# Beta22.net
KiCad netlist of a schematic drawn in EAGLE
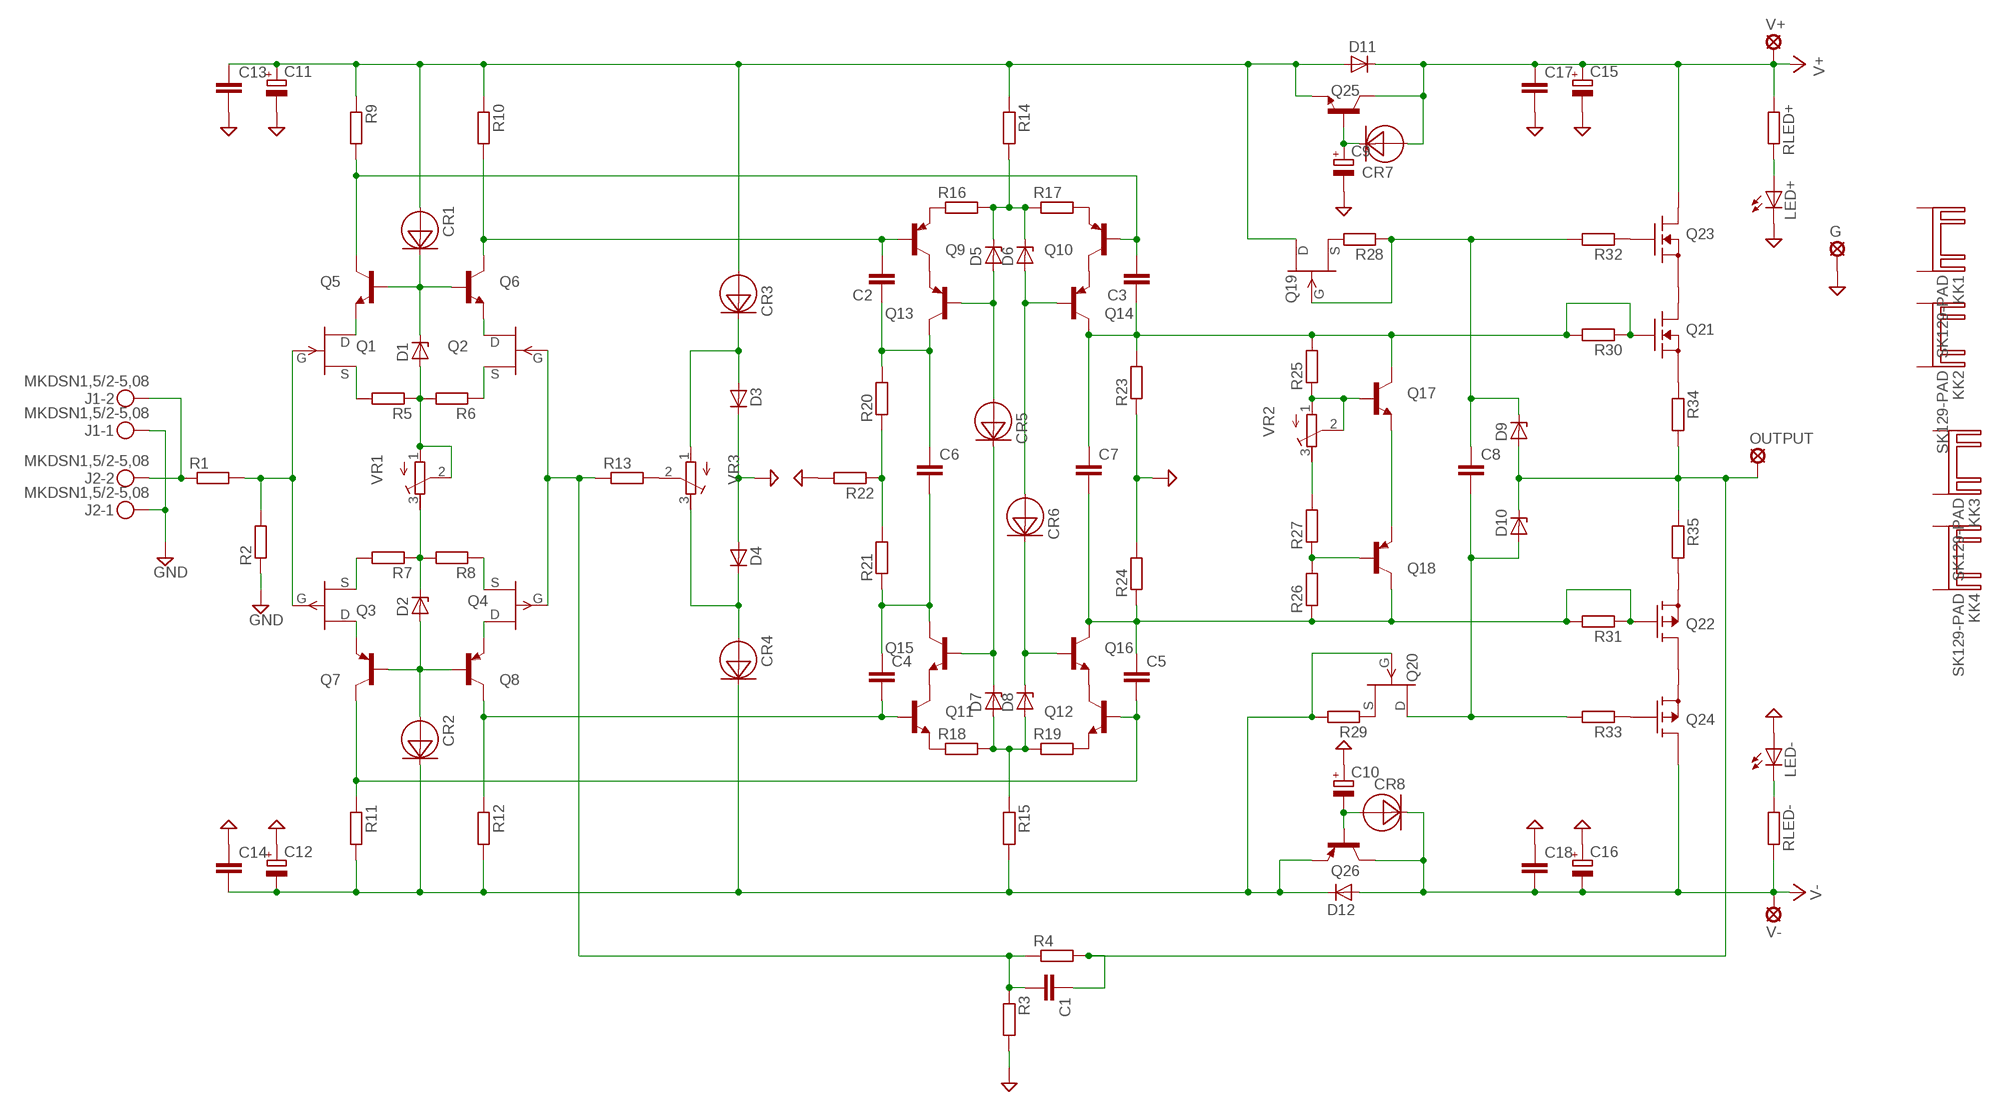
[diagram p0: schematic, sheet 1]

(export (version "E")
  (design (tool "Eeschema 10.0.6"))
  (components
    (comp (ref "C1")
      (value "C-EU025_050-025X075")
      (footprint "eagle-import:C025_050-025X075")
      (libsource (lib "eagle-import") (part "C-EU025_050-025X075"))
    )
    (comp (ref "C2")
      (value "C-EU025_050-025X075")
      (footprint "eagle-import:C025_050-025X075")
      (libsource (lib "eagle-import") (part "C-EU025_050-025X075"))
    )
    (comp (ref "C3")
      (value "C-EU025_050-025X075")
      (footprint "eagle-import:C025_050-025X075")
      (libsource (lib "eagle-import") (part "C-EU025_050-025X075"))
    )
    (comp (ref "C4")
      (value "C-EU025_050-025X075")
      (footprint "eagle-import:C025_050-025X075")
      (libsource (lib "eagle-import") (part "C-EU025_050-025X075"))
    )
    (comp (ref "C5")
      (value "C-EU025_050-025X075")
      (footprint "eagle-import:C025_050-025X075")
      (libsource (lib "eagle-import") (part "C-EU025_050-025X075"))
    )
    (comp (ref "C6")
      (value "C-EU050-055X075")
      (footprint "eagle-import:C050-055X075")
      (libsource (lib "eagle-import") (part "C-EU050-055X075"))
    )
    (comp (ref "C7")
      (value "C-EU050-055X075")
      (footprint "eagle-import:C050-055X075")
      (libsource (lib "eagle-import") (part "C-EU050-055X075"))
    )
    (comp (ref "C8")
      (value "C-EU050-055X075")
      (footprint "eagle-import:C050-055X075")
      (libsource (lib "eagle-import") (part "C-EU050-055X075"))
    )
    (comp (ref "C9")
      (value "CPOL-EUE5-13")
      (footprint "eagle-import:E5-13")
      (libsource (lib "eagle-import") (part "CPOL-EUE5-13"))
    )
    (comp (ref "C10")
      (value "CPOL-EUE5-13")
      (footprint "eagle-import:E5-13")
      (libsource (lib "eagle-import") (part "CPOL-EUE5-13"))
    )
    (comp (ref "C11")
      (value "CPOL-EUE5-13")
      (footprint "eagle-import:E5-13")
      (libsource (lib "eagle-import") (part "CPOL-EUE5-13"))
    )
    (comp (ref "C12")
      (value "CPOL-EUE5-13")
      (footprint "eagle-import:E5-13")
      (libsource (lib "eagle-import") (part "CPOL-EUE5-13"))
    )
    (comp (ref "C13")
      (value "C-EU050-055X075")
      (footprint "eagle-import:C050-055X075")
      (libsource (lib "eagle-import") (part "C-EU050-055X075"))
    )
    (comp (ref "C14")
      (value "C-EU050-055X075")
      (footprint "eagle-import:C050-055X075")
      (libsource (lib "eagle-import") (part "C-EU050-055X075"))
    )
    (comp (ref "C15")
      (value "CPOL-EUE7.5-18")
      (footprint "eagle-import:E7,5-18")
      (libsource (lib "eagle-import") (part "CPOL-EUE7.5-18"))
    )
    (comp (ref "C16")
      (value "CPOL-EUE7.5-18")
      (footprint "eagle-import:E7,5-18")
      (libsource (lib "eagle-import") (part "CPOL-EUE7.5-18"))
    )
    (comp (ref "C17")
      (value "C-EU050-055X075")
      (footprint "eagle-import:C050-055X075")
      (libsource (lib "eagle-import") (part "C-EU050-055X075"))
    )
    (comp (ref "C18")
      (value "C-EU050-055X075")
      (footprint "eagle-import:C050-055X075")
      (libsource (lib "eagle-import") (part "C-EU050-055X075"))
    )
    (comp (ref "CR1")
      (value "E-202")
      (footprint "eagle-import:DO-35-3")
      (libsource (lib "eagle-import") (part "E-202"))
    )
    (comp (ref "CR2")
      (value "E-202")
      (footprint "eagle-import:DO-35-3")
      (libsource (lib "eagle-import") (part "E-202"))
    )
    (comp (ref "CR3")
      (value "E-202")
      (footprint "eagle-import:DO-35-3")
      (libsource (lib "eagle-import") (part "E-202"))
    )
    (comp (ref "CR4")
      (value "E-202")
      (footprint "eagle-import:DO-35-3")
      (libsource (lib "eagle-import") (part "E-202"))
    )
    (comp (ref "CR5")
      (value "E-202")
      (footprint "eagle-import:DO-35-3")
      (libsource (lib "eagle-import") (part "E-202"))
    )
    (comp (ref "CR6")
      (value "E-202")
      (footprint "eagle-import:DO-35-3")
      (libsource (lib "eagle-import") (part "E-202"))
    )
    (comp (ref "CR7")
      (value "E-202")
      (footprint "eagle-import:DO-35-3")
      (libsource (lib "eagle-import") (part "E-202"))
    )
    (comp (ref "CR8")
      (value "E-202")
      (footprint "eagle-import:DO-35-3")
      (libsource (lib "eagle-import") (part "E-202"))
    )
    (comp (ref "D1")
      (value "BZV10")
      (footprint "eagle-import:DO34Z7")
      (libsource (lib "eagle-import") (part "BZV10"))
    )
    (comp (ref "D2")
      (value "BZV10")
      (footprint "eagle-import:DO34Z7")
      (libsource (lib "eagle-import") (part "BZV10"))
    )
    (comp (ref "D3")
      (value "1N4148-V")
      (footprint "eagle-import:1N4148")
      (libsource (lib "eagle-import") (part "1N4148-V"))
    )
    (comp (ref "D4")
      (value "1N4148-V")
      (footprint "eagle-import:1N4148")
      (libsource (lib "eagle-import") (part "1N4148-V"))
    )
    (comp (ref "D5")
      (value "BZV10")
      (footprint "eagle-import:DO34Z7")
      (libsource (lib "eagle-import") (part "BZV10"))
    )
    (comp (ref "D6")
      (value "BZV10")
      (footprint "eagle-import:DO34Z7")
      (libsource (lib "eagle-import") (part "BZV10"))
    )
    (comp (ref "D7")
      (value "BZV10")
      (footprint "eagle-import:DO34Z7")
      (libsource (lib "eagle-import") (part "BZV10"))
    )
    (comp (ref "D8")
      (value "BZV10")
      (footprint "eagle-import:DO34Z7")
      (libsource (lib "eagle-import") (part "BZV10"))
    )
    (comp (ref "D9")
      (value "BZV10")
      (footprint "eagle-import:DO34Z7")
      (libsource (lib "eagle-import") (part "BZV10"))
    )
    (comp (ref "D10")
      (value "BZV10")
      (footprint "eagle-import:DO34Z7")
      (libsource (lib "eagle-import") (part "BZV10"))
    )
    (comp (ref "D11")
      (value "1N4148-V")
      (footprint "eagle-import:1N4148")
      (libsource (lib "eagle-import") (part "1N4148-V"))
    )
    (comp (ref "D12")
      (value "1N4148-V")
      (footprint "eagle-import:1N4148")
      (libsource (lib "eagle-import") (part "1N4148-V"))
    )
    (comp (ref "G")
      (value "SE14")
      (footprint "eagle-import:SE14")
      (libsource (lib "eagle-import") (part "SE14"))
    )
    (comp (ref "J1")
      (value "MKDSN1,5/2-5,08")
      (footprint "eagle-import:MKDSN1,5_2-5,08")
      (libsource (lib "eagle-import") (part "MKDSN1,5/2-5,08"))
    )
    (comp (ref "J2")
      (value "MKDSN1,5/2-5,08")
      (footprint "eagle-import:MKDSN1,5_2-5,08")
      (libsource (lib "eagle-import") (part "MKDSN1,5/2-5,08"))
    )
    (comp (ref "KK1")
      (value "SK129-PAD")
      (footprint "eagle-import:SK129")
      (libsource (lib "eagle-import") (part "SK129-PAD"))
    )
    (comp (ref "KK2")
      (value "SK129-PAD")
      (footprint "eagle-import:SK129")
      (libsource (lib "eagle-import") (part "SK129-PAD"))
    )
    (comp (ref "KK3")
      (value "SK129-PAD")
      (footprint "eagle-import:SK129")
      (libsource (lib "eagle-import") (part "SK129-PAD"))
    )
    (comp (ref "KK4")
      (value "SK129-PAD")
      (footprint "eagle-import:SK129")
      (libsource (lib "eagle-import") (part "SK129-PAD"))
    )
    (comp (ref "LED+")
      (value "LED5MM")
      (footprint "eagle-import:LED5MM")
      (libsource (lib "eagle-import") (part "LED5MM"))
    )
    (comp (ref "LED-")
      (value "LED5MM")
      (footprint "eagle-import:LED5MM")
      (libsource (lib "eagle-import") (part "LED5MM"))
    )
    (comp (ref "OUTPUT")
      (value "SE14")
      (footprint "eagle-import:SE14")
      (libsource (lib "eagle-import") (part "SE14"))
    )
    (comp (ref "Q1")
      (value "2SK170")
      (footprint "eagle-import:TO92-")
      (libsource (lib "eagle-import") (part "2SK170"))
    )
    (comp (ref "Q2")
      (value "2SK170")
      (footprint "eagle-import:TO92-")
      (libsource (lib "eagle-import") (part "2SK170"))
    )
    (comp (ref "Q3")
      (value "2SJ74BL")
      (footprint "eagle-import:TO92-")
      (libsource (lib "eagle-import") (part "2SJ74BL"))
    )
    (comp (ref "Q4")
      (value "2SJ74BL")
      (footprint "eagle-import:TO92-")
      (libsource (lib "eagle-import") (part "2SJ74BL"))
    )
    (comp (ref "Q5")
      (value "BC550")
      (footprint "eagle-import:TO92-EBC")
      (libsource (lib "eagle-import") (part "BC550"))
    )
    (comp (ref "Q6")
      (value "BC550")
      (footprint "eagle-import:TO92-EBC")
      (libsource (lib "eagle-import") (part "BC550"))
    )
    (comp (ref "Q7")
      (value "BC560")
      (footprint "eagle-import:TO92_1")
      (libsource (lib "eagle-import") (part "BC560"))
    )
    (comp (ref "Q8")
      (value "BC560")
      (footprint "eagle-import:TO92_1")
      (libsource (lib "eagle-import") (part "BC560"))
    )
    (comp (ref "Q9")
      (value "BC560")
      (footprint "eagle-import:TO92_1")
      (libsource (lib "eagle-import") (part "BC560"))
    )
    (comp (ref "Q10")
      (value "BC560")
      (footprint "eagle-import:TO92_1")
      (libsource (lib "eagle-import") (part "BC560"))
    )
    (comp (ref "Q11")
      (value "BC550")
      (footprint "eagle-import:TO92-EBC")
      (libsource (lib "eagle-import") (part "BC550"))
    )
    (comp (ref "Q12")
      (value "BC550")
      (footprint "eagle-import:TO92-EBC")
      (libsource (lib "eagle-import") (part "BC550"))
    )
    (comp (ref "Q13")
      (value "BC560")
      (footprint "eagle-import:TO92_1")
      (libsource (lib "eagle-import") (part "BC560"))
    )
    (comp (ref "Q14")
      (value "BC560")
      (footprint "eagle-import:TO92_1")
      (libsource (lib "eagle-import") (part "BC560"))
    )
    (comp (ref "Q15")
      (value "BC550")
      (footprint "eagle-import:TO92-EBC")
      (libsource (lib "eagle-import") (part "BC550"))
    )
    (comp (ref "Q16")
      (value "BC550")
      (footprint "eagle-import:TO92-EBC")
      (libsource (lib "eagle-import") (part "BC550"))
    )
    (comp (ref "Q17")
      (value "BC550")
      (footprint "eagle-import:TO92-EBC")
      (libsource (lib "eagle-import") (part "BC550"))
    )
    (comp (ref "Q18")
      (value "BC560")
      (footprint "eagle-import:TO92_1")
      (libsource (lib "eagle-import") (part "BC560"))
    )
    (comp (ref "Q19")
      (value "PN4392")
      (footprint "eagle-import:TO92-")
      (libsource (lib "eagle-import") (part "PN4392"))
    )
    (comp (ref "Q20")
      (value "PN4392")
      (footprint "eagle-import:TO92-")
      (libsource (lib "eagle-import") (part "PN4392"))
    )
    (comp (ref "Q21")
      (value "IRFZ24N")
      (footprint "eagle-import:TO220V")
      (libsource (lib "eagle-import") (part "IRFZ24N"))
    )
    (comp (ref "Q22")
      (value "IRFZ34N")
      (footprint "eagle-import:TO220V")
      (libsource (lib "eagle-import") (part "IRFZ34N"))
    )
    (comp (ref "Q23")
      (value "IRFZ24N")
      (footprint "eagle-import:TO220V")
      (libsource (lib "eagle-import") (part "IRFZ24N"))
    )
    (comp (ref "Q24")
      (value "IRFZ34N")
      (footprint "eagle-import:TO220V")
      (libsource (lib "eagle-import") (part "IRFZ34N"))
    )
    (comp (ref "Q25")
      (value "BC550")
      (footprint "eagle-import:TO92-EBC")
      (libsource (lib "eagle-import") (part "BC550"))
    )
    (comp (ref "Q26")
      (value "BC560")
      (footprint "eagle-import:TO92_1")
      (libsource (lib "eagle-import") (part "BC560"))
    )
    (comp (ref "R1")
      (value "R-EU_0309/10")
      (footprint "eagle-import:0309_10")
      (libsource (lib "eagle-import") (part "R-EU_0309/10"))
    )
    (comp (ref "R2")
      (value "R-EU_0309/10")
      (footprint "eagle-import:0309_10")
      (libsource (lib "eagle-import") (part "R-EU_0309/10"))
    )
    (comp (ref "R3")
      (value "R-EU_0309/10")
      (footprint "eagle-import:0309_10")
      (libsource (lib "eagle-import") (part "R-EU_0309/10"))
    )
    (comp (ref "R4")
      (value "R-EU_0309/10")
      (footprint "eagle-import:0309_10")
      (libsource (lib "eagle-import") (part "R-EU_0309/10"))
    )
    (comp (ref "R5")
      (value "R-EU_0309/10")
      (footprint "eagle-import:0309_10")
      (libsource (lib "eagle-import") (part "R-EU_0309/10"))
    )
    (comp (ref "R6")
      (value "R-EU_0309/10")
      (footprint "eagle-import:0309_10")
      (libsource (lib "eagle-import") (part "R-EU_0309/10"))
    )
    (comp (ref "R7")
      (value "R-EU_0309/10")
      (footprint "eagle-import:0309_10")
      (libsource (lib "eagle-import") (part "R-EU_0309/10"))
    )
    (comp (ref "R8")
      (value "R-EU_0309/10")
      (footprint "eagle-import:0309_10")
      (libsource (lib "eagle-import") (part "R-EU_0309/10"))
    )
    (comp (ref "R9")
      (value "R-EU_0309/10")
      (footprint "eagle-import:0309_10")
      (libsource (lib "eagle-import") (part "R-EU_0309/10"))
    )
    (comp (ref "R10")
      (value "R-EU_0309/10")
      (footprint "eagle-import:0309_10")
      (libsource (lib "eagle-import") (part "R-EU_0309/10"))
    )
    (comp (ref "R11")
      (value "R-EU_0309/10")
      (footprint "eagle-import:0309_10")
      (libsource (lib "eagle-import") (part "R-EU_0309/10"))
    )
    (comp (ref "R12")
      (value "R-EU_0309/10")
      (footprint "eagle-import:0309_10")
      (libsource (lib "eagle-import") (part "R-EU_0309/10"))
    )
    (comp (ref "R13")
      (value "R-EU_0309/10")
      (footprint "eagle-import:0309_10")
      (libsource (lib "eagle-import") (part "R-EU_0309/10"))
    )
    (comp (ref "R14")
      (value "R-EU_0309/10")
      (footprint "eagle-import:0309_10")
      (libsource (lib "eagle-import") (part "R-EU_0309/10"))
    )
    (comp (ref "R15")
      (value "R-EU_0309/10")
      (footprint "eagle-import:0309_10")
      (libsource (lib "eagle-import") (part "R-EU_0309/10"))
    )
    (comp (ref "R16")
      (value "R-EU_0309/10")
      (footprint "eagle-import:0309_10")
      (libsource (lib "eagle-import") (part "R-EU_0309/10"))
    )
    (comp (ref "R17")
      (value "R-EU_0309/10")
      (footprint "eagle-import:0309_10")
      (libsource (lib "eagle-import") (part "R-EU_0309/10"))
    )
    (comp (ref "R18")
      (value "R-EU_0309/10")
      (footprint "eagle-import:0309_10")
      (libsource (lib "eagle-import") (part "R-EU_0309/10"))
    )
    (comp (ref "R19")
      (value "R-EU_0309/10")
      (footprint "eagle-import:0309_10")
      (libsource (lib "eagle-import") (part "R-EU_0309/10"))
    )
    (comp (ref "R20")
      (value "R-EU_0309/10")
      (footprint "eagle-import:0309_10")
      (libsource (lib "eagle-import") (part "R-EU_0309/10"))
    )
    (comp (ref "R21")
      (value "R-EU_0309/10")
      (footprint "eagle-import:0309_10")
      (libsource (lib "eagle-import") (part "R-EU_0309/10"))
    )
    (comp (ref "R22")
      (value "R-EU_0309/10")
      (footprint "eagle-import:0309_10")
      (libsource (lib "eagle-import") (part "R-EU_0309/10"))
    )
    (comp (ref "R23")
      (value "R-EU_0309/10")
      (footprint "eagle-import:0309_10")
      (libsource (lib "eagle-import") (part "R-EU_0309/10"))
    )
    (comp (ref "R24")
      (value "R-EU_0309/10")
      (footprint "eagle-import:0309_10")
      (libsource (lib "eagle-import") (part "R-EU_0309/10"))
    )
    (comp (ref "R25")
      (value "R-EU_0309/10")
      (footprint "eagle-import:0309_10")
      (libsource (lib "eagle-import") (part "R-EU_0309/10"))
    )
    (comp (ref "R26")
      (value "R-EU_0309/10")
      (footprint "eagle-import:0309_10")
      (libsource (lib "eagle-import") (part "R-EU_0309/10"))
    )
    (comp (ref "R27")
      (value "R-EU_0309/10")
      (footprint "eagle-import:0309_10")
      (libsource (lib "eagle-import") (part "R-EU_0309/10"))
    )
    (comp (ref "R28")
      (value "R-EU_0309/10")
      (footprint "eagle-import:0309_10")
      (libsource (lib "eagle-import") (part "R-EU_0309/10"))
    )
    (comp (ref "R29")
      (value "R-EU_0309/10")
      (footprint "eagle-import:0309_10")
      (libsource (lib "eagle-import") (part "R-EU_0309/10"))
    )
    (comp (ref "R30")
      (value "R-EU_0309/10")
      (footprint "eagle-import:0309_10")
      (libsource (lib "eagle-import") (part "R-EU_0309/10"))
    )
    (comp (ref "R31")
      (value "R-EU_0309/10")
      (footprint "eagle-import:0309_10")
      (libsource (lib "eagle-import") (part "R-EU_0309/10"))
    )
    (comp (ref "R32")
      (value "R-EU_0309/10")
      (footprint "eagle-import:0309_10")
      (libsource (lib "eagle-import") (part "R-EU_0309/10"))
    )
    (comp (ref "R33")
      (value "R-EU_0309/10")
      (footprint "eagle-import:0309_10")
      (libsource (lib "eagle-import") (part "R-EU_0309/10"))
    )
    (comp (ref "R34")
      (value "R-EU_0617/17")
      (footprint "eagle-import:0617_17")
      (libsource (lib "eagle-import") (part "R-EU_0617/17"))
    )
    (comp (ref "R35")
      (value "R-EU_0617/17")
      (footprint "eagle-import:0617_17")
      (libsource (lib "eagle-import") (part "R-EU_0617/17"))
    )
    (comp (ref "RLED+")
      (value "R-EU_0309/10")
      (footprint "eagle-import:0309_10")
      (libsource (lib "eagle-import") (part "R-EU_0309/10"))
    )
    (comp (ref "RLED-")
      (value "R-EU_0309/10")
      (footprint "eagle-import:0309_10")
      (libsource (lib "eagle-import") (part "R-EU_0309/10"))
    )
    (comp (ref "V+")
      (value "SE14")
      (footprint "eagle-import:SE14")
      (libsource (lib "eagle-import") (part "SE14"))
    )
    (comp (ref "V-")
      (value "SE14")
      (footprint "eagle-import:SE14")
      (libsource (lib "eagle-import") (part "SE14"))
    )
    (comp (ref "VR1")
      (value "R-TRIMM3296W")
      (footprint "eagle-import:RTRIM3296W")
      (libsource (lib "eagle-import") (part "R-TRIMM3296W"))
    )
    (comp (ref "VR2")
      (value "R-TRIMM3296W")
      (footprint "eagle-import:RTRIM3296W")
      (libsource (lib "eagle-import") (part "R-TRIMM3296W"))
    )
    (comp (ref "VR3")
      (value "R-TRIMM3296W")
      (footprint "eagle-import:RTRIM3296W")
      (libsource (lib "eagle-import") (part "R-TRIMM3296W"))
    )
  )
  (nets
    (net (code "1") (name "GND") (class "Default")
      (node (ref "C10") (pin "+") (pinfunction "+_+") (pintype "passive"))
      (node (ref "C11") (pin "-") (pinfunction "-_-") (pintype "passive"))
      (node (ref "C12") (pin "+") (pinfunction "+_+") (pintype "passive"))
      (node (ref "C13") (pin "2") (pinfunction "2_2") (pintype "passive"))
      (node (ref "C14") (pin "1") (pinfunction "1_1") (pintype "passive"))
      (node (ref "C15") (pin "-") (pinfunction "-_-") (pintype "passive"))
      (node (ref "C16") (pin "+") (pinfunction "+_+") (pintype "passive"))
      (node (ref "C17") (pin "2") (pinfunction "2_2") (pintype "passive"))
      (node (ref "C18") (pin "1") (pinfunction "1_1") (pintype "passive"))
      (node (ref "C9") (pin "-") (pinfunction "-_-") (pintype "passive"))
      (node (ref "D3") (pin "C") (pinfunction "C_C") (pintype "passive"))
      (node (ref "D4") (pin "A") (pinfunction "A_A") (pintype "passive"))
      (node (ref "G") (pin "MP") (pinfunction "MP_MP") (pintype "passive"))
      (node (ref "J1") (pin "1") (pinfunction "KL_1") (pintype "passive"))
      (node (ref "J2") (pin "1") (pinfunction "KL_1") (pintype "passive"))
      (node (ref "LED+") (pin "K") (pinfunction "C_K") (pintype "passive"))
      (node (ref "LED-") (pin "A") (pinfunction "A_A") (pintype "passive"))
      (node (ref "R2") (pin "1") (pinfunction "1_1") (pintype "passive"))
      (node (ref "R22") (pin "2") (pinfunction "2_2") (pintype "passive"))
      (node (ref "R23") (pin "1") (pinfunction "1_1") (pintype "passive"))
      (node (ref "R24") (pin "2") (pinfunction "2_2") (pintype "passive"))
      (node (ref "R3") (pin "2") (pinfunction "2_2") (pintype "passive"))
    )
    (net (code "2") (name "Net-(C1-Pad1)") (class "Default")
      (node (ref "C1") (pin "1") (pinfunction "1_1") (pintype "passive"))
      (node (ref "D10") (pin "C") (pinfunction "C_C") (pintype "passive"))
      (node (ref "D9") (pin "A") (pinfunction "A_A") (pintype "passive"))
      (node (ref "OUTPUT") (pin "MP") (pinfunction "MP_MP") (pintype "passive"))
      (node (ref "R34") (pin "2") (pinfunction "2_2") (pintype "passive"))
      (node (ref "R35") (pin "1") (pinfunction "1_1") (pintype "passive"))
      (node (ref "R4") (pin "2") (pinfunction "2_2") (pintype "passive"))
    )
    (net (code "3") (name "Net-(C4-Pad1)") (class "Default")
      (node (ref "C4") (pin "1") (pinfunction "1_1") (pintype "passive"))
      (node (ref "C6") (pin "2") (pinfunction "2_2") (pintype "passive"))
      (node (ref "Q15") (pin "C") (pinfunction "C_C") (pintype "passive"))
      (node (ref "R21") (pin "1") (pinfunction "1_1") (pintype "passive"))
    )
    (net (code "4") (name "Net-(C9-Pad+)") (class "Default")
      (node (ref "C9") (pin "+") (pinfunction "+_+") (pintype "passive"))
      (node (ref "CR7") (pin "1") (pinfunction "CATHODE_1") (pintype "passive"))
      (node (ref "CR7") (pin "2") (pinfunction "CATHODE_2") (pintype "passive"))
      (node (ref "CR7") (pin "CATHODE") (pinfunction "CATHODE_CATHODE") (pintype "passive"))
      (node (ref "Q25") (pin "B") (pinfunction "B_B") (pintype "passive"))
    )
    (net (code "5") (name "Net-(CR1-CATHODE-Pad1)") (class "Default")
      (node (ref "CR1") (pin "1") (pinfunction "CATHODE_1") (pintype "passive"))
      (node (ref "CR1") (pin "2") (pinfunction "CATHODE_2") (pintype "passive"))
      (node (ref "CR1") (pin "CATHODE") (pinfunction "CATHODE_CATHODE") (pintype "passive"))
      (node (ref "D1") (pin "C") (pinfunction "C_C") (pintype "passive"))
      (node (ref "Q5") (pin "B") (pinfunction "B_B") (pintype "passive"))
      (node (ref "Q6") (pin "B") (pinfunction "B_B") (pintype "passive"))
    )
    (net (code "6") (name "Net-(CR5-CATHODE-Pad1)") (class "Default")
      (node (ref "CR5") (pin "1") (pinfunction "CATHODE_1") (pintype "passive"))
      (node (ref "CR5") (pin "2") (pinfunction "CATHODE_2") (pintype "passive"))
      (node (ref "CR5") (pin "CATHODE") (pinfunction "CATHODE_CATHODE") (pintype "passive"))
      (node (ref "D7") (pin "C") (pinfunction "C_C") (pintype "passive"))
      (node (ref "Q15") (pin "B") (pinfunction "B_B") (pintype "passive"))
    )
    (net (code "7") (name "Net-(CR6-CATHODE-Pad1)") (class "Default")
      (node (ref "CR6") (pin "1") (pinfunction "CATHODE_1") (pintype "passive"))
      (node (ref "CR6") (pin "2") (pinfunction "CATHODE_2") (pintype "passive"))
      (node (ref "CR6") (pin "CATHODE") (pinfunction "CATHODE_CATHODE") (pintype "passive"))
      (node (ref "D8") (pin "C") (pinfunction "C_C") (pintype "passive"))
      (node (ref "Q16") (pin "B") (pinfunction "B_B") (pintype "passive"))
    )
    (net (code "8") (name "Net-(D5-PadC)") (class "Default")
      (node (ref "D5") (pin "C") (pinfunction "C_C") (pintype "passive"))
      (node (ref "D6") (pin "C") (pinfunction "C_C") (pintype "passive"))
      (node (ref "R14") (pin "2") (pinfunction "2_2") (pintype "passive"))
      (node (ref "R16") (pin "2") (pinfunction "2_2") (pintype "passive"))
      (node (ref "R17") (pin "1") (pinfunction "1_1") (pintype "passive"))
    )
    (net (code "9") (name "Net-(D7-PadA)") (class "Default")
      (node (ref "D7") (pin "A") (pinfunction "A_A") (pintype "passive"))
      (node (ref "D8") (pin "A") (pinfunction "A_A") (pintype "passive"))
      (node (ref "R15") (pin "1") (pinfunction "1_1") (pintype "passive"))
      (node (ref "R18") (pin "2") (pinfunction "2_2") (pintype "passive"))
      (node (ref "R19") (pin "1") (pinfunction "1_1") (pintype "passive"))
    )
    (net (code "10") (name "Net-(J1B-KL)") (class "Default")
      (node (ref "J1") (pin "2") (pinfunction "KL_2") (pintype "passive"))
      (node (ref "J2") (pin "2") (pinfunction "KL_2") (pintype "passive"))
      (node (ref "R1") (pin "1") (pinfunction "1_1") (pintype "passive"))
    )
    (net (code "11") (name "Net-(LED+-PadA)") (class "Default")
      (node (ref "LED+") (pin "A") (pinfunction "A_A") (pintype "passive"))
      (node (ref "RLED+") (pin "2") (pinfunction "2_2") (pintype "passive"))
    )
    (net (code "12") (name "Net-(LED--C)") (class "Default")
      (node (ref "LED-") (pin "K") (pinfunction "C_K") (pintype "passive"))
      (node (ref "RLED-") (pin "1") (pinfunction "1_1") (pintype "passive"))
    )
    (net (code "13") (name "Net-(Q1-D)") (class "Default")
      (node (ref "Q1") (pin "1") (pinfunction "D_1") (pintype "passive"))
      (node (ref "Q5") (pin "E") (pinfunction "E_E") (pintype "passive"))
    )
    (net (code "14") (name "Net-(Q1-G)") (class "Default")
      (node (ref "Q1") (pin "2") (pinfunction "G_2") (pintype "passive"))
      (node (ref "Q3") (pin "2") (pinfunction "G_2") (pintype "passive"))
      (node (ref "R1") (pin "2") (pinfunction "2_2") (pintype "passive"))
      (node (ref "R2") (pin "2") (pinfunction "2_2") (pintype "passive"))
    )
    (net (code "15") (name "Net-(Q1-S)") (class "Default")
      (node (ref "Q1") (pin "3") (pinfunction "S_3") (pintype "passive"))
      (node (ref "R5") (pin "2") (pinfunction "2_2") (pintype "passive"))
    )
    (net (code "16") (name "Net-(Q2-D)") (class "Default")
      (node (ref "Q2") (pin "1") (pinfunction "D_1") (pintype "passive"))
      (node (ref "Q6") (pin "E") (pinfunction "E_E") (pintype "passive"))
    )
    (net (code "17") (name "Net-(Q2-G)") (class "Default")
      (node (ref "C1") (pin "2") (pinfunction "2_2") (pintype "passive"))
      (node (ref "C1") (pin "3") (pinfunction "2_3") (pintype "passive"))
      (node (ref "Q2") (pin "2") (pinfunction "G_2") (pintype "passive"))
      (node (ref "Q4") (pin "2") (pinfunction "G_2") (pintype "passive"))
      (node (ref "R13") (pin "1") (pinfunction "1_1") (pintype "passive"))
      (node (ref "R3") (pin "1") (pinfunction "1_1") (pintype "passive"))
      (node (ref "R4") (pin "1") (pinfunction "1_1") (pintype "passive"))
    )
    (net (code "18") (name "Net-(Q2-S)") (class "Default")
      (node (ref "Q2") (pin "3") (pinfunction "S_3") (pintype "passive"))
      (node (ref "R6") (pin "1") (pinfunction "1_1") (pintype "passive"))
    )
    (net (code "19") (name "Net-(Q3-D)") (class "Default")
      (node (ref "Q3") (pin "1") (pinfunction "D_1") (pintype "passive"))
      (node (ref "Q7") (pin "3") (pinfunction "E_3") (pintype "passive"))
    )
    (net (code "20") (name "Net-(Q3-S)") (class "Default")
      (node (ref "Q3") (pin "3") (pinfunction "S_3") (pintype "passive"))
      (node (ref "R7") (pin "2") (pinfunction "2_2") (pintype "passive"))
    )
    (net (code "21") (name "Net-(Q4-D)") (class "Default")
      (node (ref "Q4") (pin "1") (pinfunction "D_1") (pintype "passive"))
      (node (ref "Q8") (pin "3") (pinfunction "E_3") (pintype "passive"))
    )
    (net (code "22") (name "Net-(Q4-S)") (class "Default")
      (node (ref "Q4") (pin "3") (pinfunction "S_3") (pintype "passive"))
      (node (ref "R8") (pin "1") (pinfunction "1_1") (pintype "passive"))
    )
    (net (code "23") (name "Net-(Q7-B)") (class "Default")
      (node (ref "CR2") (pin "ANODE") (pinfunction "ANODE_ANODE") (pintype "passive"))
      (node (ref "D2") (pin "A") (pinfunction "A_A") (pintype "passive"))
      (node (ref "Q7") (pin "2") (pinfunction "B_2") (pintype "passive"))
      (node (ref "Q8") (pin "2") (pinfunction "B_2") (pintype "passive"))
    )
    (net (code "24") (name "Net-(Q7-C)") (class "Default")
      (node (ref "C5") (pin "2") (pinfunction "2_2") (pintype "passive"))
      (node (ref "C5") (pin "3") (pinfunction "2_3") (pintype "passive"))
      (node (ref "Q12") (pin "B") (pinfunction "B_B") (pintype "passive"))
      (node (ref "Q7") (pin "1") (pinfunction "C_1") (pintype "passive"))
      (node (ref "R11") (pin "1") (pinfunction "1_1") (pintype "passive"))
    )
    (net (code "25") (name "Net-(Q8-C)") (class "Default")
      (node (ref "C4") (pin "2") (pinfunction "2_2") (pintype "passive"))
      (node (ref "C4") (pin "3") (pinfunction "2_3") (pintype "passive"))
      (node (ref "Q11") (pin "B") (pinfunction "B_B") (pintype "passive"))
      (node (ref "Q8") (pin "1") (pinfunction "C_1") (pintype "passive"))
      (node (ref "R12") (pin "1") (pinfunction "1_1") (pintype "passive"))
    )
    (net (code "26") (name "Net-(Q9-B)") (class "Default")
      (node (ref "C2") (pin "2") (pinfunction "2_2") (pintype "passive"))
      (node (ref "C2") (pin "3") (pinfunction "2_3") (pintype "passive"))
      (node (ref "Q6") (pin "C") (pinfunction "C_C") (pintype "passive"))
      (node (ref "Q9") (pin "2") (pinfunction "B_2") (pintype "passive"))
      (node (ref "R10") (pin "2") (pinfunction "2_2") (pintype "passive"))
    )
    (net (code "27") (name "Net-(Q9-E)") (class "Default")
      (node (ref "Q9") (pin "3") (pinfunction "E_3") (pintype "passive"))
      (node (ref "R16") (pin "1") (pinfunction "1_1") (pintype "passive"))
    )
    (net (code "28") (name "Net-(Q10-B)") (class "Default")
      (node (ref "C3") (pin "2") (pinfunction "2_2") (pintype "passive"))
      (node (ref "C3") (pin "3") (pinfunction "2_3") (pintype "passive"))
      (node (ref "Q10") (pin "2") (pinfunction "B_2") (pintype "passive"))
      (node (ref "Q5") (pin "C") (pinfunction "C_C") (pintype "passive"))
      (node (ref "R9") (pin "2") (pinfunction "2_2") (pintype "passive"))
    )
    (net (code "29") (name "Net-(Q10-C)") (class "Default")
      (node (ref "Q10") (pin "1") (pinfunction "C_1") (pintype "passive"))
      (node (ref "Q14") (pin "3") (pinfunction "E_3") (pintype "passive"))
    )
    (net (code "30") (name "Net-(Q10-E)") (class "Default")
      (node (ref "Q10") (pin "3") (pinfunction "E_3") (pintype "passive"))
      (node (ref "R17") (pin "2") (pinfunction "2_2") (pintype "passive"))
    )
    (net (code "31") (name "Net-(Q11-PadC)") (class "Default")
      (node (ref "Q11") (pin "C") (pinfunction "C_C") (pintype "passive"))
      (node (ref "Q15") (pin "E") (pinfunction "E_E") (pintype "passive"))
    )
    (net (code "32") (name "Net-(Q11-PadE)") (class "Default")
      (node (ref "Q11") (pin "E") (pinfunction "E_E") (pintype "passive"))
      (node (ref "R18") (pin "1") (pinfunction "1_1") (pintype "passive"))
    )
    (net (code "33") (name "Net-(Q12-PadC)") (class "Default")
      (node (ref "Q12") (pin "C") (pinfunction "C_C") (pintype "passive"))
      (node (ref "Q16") (pin "E") (pinfunction "E_E") (pintype "passive"))
    )
    (net (code "34") (name "Net-(Q12-PadE)") (class "Default")
      (node (ref "Q12") (pin "E") (pinfunction "E_E") (pintype "passive"))
      (node (ref "R19") (pin "2") (pinfunction "2_2") (pintype "passive"))
    )
    (net (code "35") (name "Net-(Q13-B)") (class "Default")
      (node (ref "CR5") (pin "ANODE") (pinfunction "ANODE_ANODE") (pintype "passive"))
      (node (ref "D5") (pin "A") (pinfunction "A_A") (pintype "passive"))
      (node (ref "Q13") (pin "2") (pinfunction "B_2") (pintype "passive"))
    )
    (net (code "36") (name "Net-(Q13-C)") (class "Default")
      (node (ref "C2") (pin "1") (pinfunction "1_1") (pintype "passive"))
      (node (ref "C6") (pin "1") (pinfunction "1_1") (pintype "passive"))
      (node (ref "Q13") (pin "1") (pinfunction "C_1") (pintype "passive"))
      (node (ref "R20") (pin "2") (pinfunction "2_2") (pintype "passive"))
    )
    (net (code "37") (name "Net-(Q13-E)") (class "Default")
      (node (ref "Q13") (pin "3") (pinfunction "E_3") (pintype "passive"))
      (node (ref "Q9") (pin "1") (pinfunction "C_1") (pintype "passive"))
    )
    (net (code "38") (name "Net-(Q14-B)") (class "Default")
      (node (ref "CR6") (pin "ANODE") (pinfunction "ANODE_ANODE") (pintype "passive"))
      (node (ref "D6") (pin "A") (pinfunction "A_A") (pintype "passive"))
      (node (ref "Q14") (pin "2") (pinfunction "B_2") (pintype "passive"))
    )
    (net (code "39") (name "Net-(Q14-C)") (class "Default")
      (node (ref "C3") (pin "1") (pinfunction "1_1") (pintype "passive"))
      (node (ref "C7") (pin "1") (pinfunction "1_1") (pintype "passive"))
      (node (ref "Q14") (pin "1") (pinfunction "C_1") (pintype "passive"))
      (node (ref "Q17") (pin "C") (pinfunction "C_C") (pintype "passive"))
      (node (ref "Q21") (pin "1") (pinfunction "G_1") (pintype "passive"))
      (node (ref "R23") (pin "2") (pinfunction "2_2") (pintype "passive"))
      (node (ref "R25") (pin "2") (pinfunction "2_2") (pintype "passive"))
      (node (ref "R30") (pin "1") (pinfunction "1_1") (pintype "passive"))
      (node (ref "R30") (pin "2") (pinfunction "2_2") (pintype "passive"))
    )
    (net (code "40") (name "Net-(Q18-B)") (class "Default")
      (node (ref "Q18") (pin "2") (pinfunction "B_2") (pintype "passive"))
      (node (ref "R26") (pin "2") (pinfunction "2_2") (pintype "passive"))
      (node (ref "R27") (pin "1") (pinfunction "1_1") (pintype "passive"))
    )
    (net (code "41") (name "Net-(Q18-C)") (class "Default")
      (node (ref "C5") (pin "1") (pinfunction "1_1") (pintype "passive"))
      (node (ref "C7") (pin "2") (pinfunction "2_2") (pintype "passive"))
      (node (ref "Q16") (pin "C") (pinfunction "C_C") (pintype "passive"))
      (node (ref "Q18") (pin "1") (pinfunction "C_1") (pintype "passive"))
      (node (ref "Q22") (pin "1") (pinfunction "G_1") (pintype "passive"))
      (node (ref "R24") (pin "1") (pinfunction "1_1") (pintype "passive"))
      (node (ref "R26") (pin "1") (pinfunction "1_1") (pintype "passive"))
      (node (ref "R31") (pin "1") (pinfunction "1_1") (pintype "passive"))
      (node (ref "R31") (pin "2") (pinfunction "2_2") (pintype "passive"))
    )
    (net (code "42") (name "Net-(Q18-E)") (class "Default")
      (node (ref "Q17") (pin "E") (pinfunction "E_E") (pintype "passive"))
      (node (ref "Q18") (pin "3") (pinfunction "E_3") (pintype "passive"))
    )
    (net (code "43") (name "Net-(Q19-D)") (class "Default")
      (node (ref "C11") (pin "+") (pinfunction "+_+") (pintype "passive"))
      (node (ref "C13") (pin "1") (pinfunction "1_1") (pintype "passive"))
      (node (ref "CR1") (pin "ANODE") (pinfunction "ANODE_ANODE") (pintype "passive"))
      (node (ref "CR3") (pin "ANODE") (pinfunction "ANODE_ANODE") (pintype "passive"))
      (node (ref "D11") (pin "A") (pinfunction "A_A") (pintype "passive"))
      (node (ref "Q19") (pin "3") (pinfunction "D_3") (pintype "passive"))
      (node (ref "Q25") (pin "E") (pinfunction "E_E") (pintype "passive"))
      (node (ref "R10") (pin "1") (pinfunction "1_1") (pintype "passive"))
      (node (ref "R14") (pin "1") (pinfunction "1_1") (pintype "passive"))
      (node (ref "R9") (pin "1") (pinfunction "1_1") (pintype "passive"))
    )
    (net (code "44") (name "Net-(Q19-G)") (class "Default")
      (node (ref "C8") (pin "1") (pinfunction "1_1") (pintype "passive"))
      (node (ref "D9") (pin "C") (pinfunction "C_C") (pintype "passive"))
      (node (ref "Q19") (pin "1") (pinfunction "G_1") (pintype "passive"))
      (node (ref "R28") (pin "1") (pinfunction "1_1") (pintype "passive"))
      (node (ref "R32") (pin "2") (pinfunction "2_2") (pintype "passive"))
    )
    (net (code "45") (name "Net-(Q19-S)") (class "Default")
      (node (ref "Q19") (pin "2") (pinfunction "S_2") (pintype "passive"))
      (node (ref "R28") (pin "2") (pinfunction "2_2") (pintype "passive"))
    )
    (net (code "46") (name "Net-(Q20-D)") (class "Default")
      (node (ref "C8") (pin "2") (pinfunction "2_2") (pintype "passive"))
      (node (ref "D10") (pin "A") (pinfunction "A_A") (pintype "passive"))
      (node (ref "Q20") (pin "3") (pinfunction "D_3") (pintype "passive"))
      (node (ref "R33") (pin "2") (pinfunction "2_2") (pintype "passive"))
    )
    (net (code "47") (name "Net-(Q20-G)") (class "Default")
      (node (ref "C12") (pin "-") (pinfunction "-_-") (pintype "passive"))
      (node (ref "C14") (pin "2") (pinfunction "2_2") (pintype "passive"))
      (node (ref "CR2") (pin "1") (pinfunction "CATHODE_1") (pintype "passive"))
      (node (ref "CR2") (pin "2") (pinfunction "CATHODE_2") (pintype "passive"))
      (node (ref "CR2") (pin "CATHODE") (pinfunction "CATHODE_CATHODE") (pintype "passive"))
      (node (ref "CR4") (pin "1") (pinfunction "CATHODE_1") (pintype "passive"))
      (node (ref "CR4") (pin "2") (pinfunction "CATHODE_2") (pintype "passive"))
      (node (ref "CR4") (pin "CATHODE") (pinfunction "CATHODE_CATHODE") (pintype "passive"))
      (node (ref "D12") (pin "C") (pinfunction "C_C") (pintype "passive"))
      (node (ref "Q20") (pin "1") (pinfunction "G_1") (pintype "passive"))
      (node (ref "Q26") (pin "3") (pinfunction "E_3") (pintype "passive"))
      (node (ref "R11") (pin "2") (pinfunction "2_2") (pintype "passive"))
      (node (ref "R12") (pin "2") (pinfunction "2_2") (pintype "passive"))
      (node (ref "R15") (pin "2") (pinfunction "2_2") (pintype "passive"))
      (node (ref "R29") (pin "2") (pinfunction "2_2") (pintype "passive"))
    )
    (net (code "48") (name "Net-(Q20-S)") (class "Default")
      (node (ref "Q20") (pin "2") (pinfunction "S_2") (pintype "passive"))
      (node (ref "R29") (pin "1") (pinfunction "1_1") (pintype "passive"))
    )
    (net (code "49") (name "Net-(Q21-D)") (class "Default")
      (node (ref "Q21") (pin "2") (pinfunction "D_2") (pintype "passive"))
      (node (ref "Q23") (pin "3") (pinfunction "S_3") (pintype "passive"))
    )
    (net (code "50") (name "Net-(Q21-S)") (class "Default")
      (node (ref "Q21") (pin "3") (pinfunction "S_3") (pintype "passive"))
      (node (ref "R34") (pin "1") (pinfunction "1_1") (pintype "passive"))
    )
    (net (code "51") (name "Net-(Q22-D)") (class "Default")
      (node (ref "Q22") (pin "2") (pinfunction "D_2") (pintype "passive"))
      (node (ref "Q24") (pin "3") (pinfunction "S_3") (pintype "passive"))
    )
    (net (code "52") (name "Net-(Q22-S)") (class "Default")
      (node (ref "Q22") (pin "3") (pinfunction "S_3") (pintype "passive"))
      (node (ref "R35") (pin "2") (pinfunction "2_2") (pintype "passive"))
    )
    (net (code "53") (name "Net-(Q23-G)") (class "Default")
      (node (ref "Q23") (pin "1") (pinfunction "G_1") (pintype "passive"))
      (node (ref "R32") (pin "1") (pinfunction "1_1") (pintype "passive"))
    )
    (net (code "54") (name "Net-(Q24-G)") (class "Default")
      (node (ref "Q24") (pin "1") (pinfunction "G_1") (pintype "passive"))
      (node (ref "R33") (pin "1") (pinfunction "1_1") (pintype "passive"))
    )
    (net (code "55") (name "Net-(Q26-B)") (class "Default")
      (node (ref "C10") (pin "-") (pinfunction "-_-") (pintype "passive"))
      (node (ref "CR8") (pin "ANODE") (pinfunction "ANODE_ANODE") (pintype "passive"))
      (node (ref "Q26") (pin "2") (pinfunction "B_2") (pintype "passive"))
    )
    (net (code "56") (name "Net-(R20-Pad1)") (class "Default")
      (node (ref "R20") (pin "1") (pinfunction "1_1") (pintype "passive"))
      (node (ref "R21") (pin "2") (pinfunction "2_2") (pintype "passive"))
      (node (ref "R22") (pin "1") (pinfunction "1_1") (pintype "passive"))
    )
    (net (code "57") (name "Net-(VR1-A)") (class "Default")
      (node (ref "D1") (pin "A") (pinfunction "A_A") (pintype "passive"))
      (node (ref "R5") (pin "1") (pinfunction "1_1") (pintype "passive"))
      (node (ref "R6") (pin "2") (pinfunction "2_2") (pintype "passive"))
      (node (ref "VR1") (pin "1") (pinfunction "A_1") (pintype "passive"))
      (node (ref "VR1") (pin "2") (pinfunction "S_2") (pintype "passive"))
    )
    (net (code "58") (name "Net-(VR1-E)") (class "Default")
      (node (ref "D2") (pin "C") (pinfunction "C_C") (pintype "passive"))
      (node (ref "R7") (pin "1") (pinfunction "1_1") (pintype "passive"))
      (node (ref "R8") (pin "2") (pinfunction "2_2") (pintype "passive"))
      (node (ref "VR1") (pin "3") (pinfunction "E_3") (pintype "passive"))
    )
    (net (code "59") (name "Net-(VR2-A)") (class "Default")
      (node (ref "Q17") (pin "B") (pinfunction "B_B") (pintype "passive"))
      (node (ref "R25") (pin "1") (pinfunction "1_1") (pintype "passive"))
      (node (ref "VR2") (pin "1") (pinfunction "A_1") (pintype "passive"))
      (node (ref "VR2") (pin "2") (pinfunction "S_2") (pintype "passive"))
    )
    (net (code "60") (name "Net-(VR2-E)") (class "Default")
      (node (ref "R27") (pin "2") (pinfunction "2_2") (pintype "passive"))
      (node (ref "VR2") (pin "3") (pinfunction "E_3") (pintype "passive"))
    )
    (net (code "61") (name "Net-(VR3-A)") (class "Default")
      (node (ref "CR3") (pin "1") (pinfunction "CATHODE_1") (pintype "passive"))
      (node (ref "CR3") (pin "2") (pinfunction "CATHODE_2") (pintype "passive"))
      (node (ref "CR3") (pin "CATHODE") (pinfunction "CATHODE_CATHODE") (pintype "passive"))
      (node (ref "D3") (pin "A") (pinfunction "A_A") (pintype "passive"))
      (node (ref "VR3") (pin "1") (pinfunction "A_1") (pintype "passive"))
    )
    (net (code "62") (name "Net-(VR3-E)") (class "Default")
      (node (ref "CR4") (pin "ANODE") (pinfunction "ANODE_ANODE") (pintype "passive"))
      (node (ref "D4") (pin "C") (pinfunction "C_C") (pintype "passive"))
      (node (ref "VR3") (pin "3") (pinfunction "E_3") (pintype "passive"))
    )
    (net (code "63") (name "Net-(VR3-S)") (class "Default")
      (node (ref "R13") (pin "2") (pinfunction "2_2") (pintype "passive"))
      (node (ref "VR3") (pin "2") (pinfunction "S_2") (pintype "passive"))
    )
    (net (code "64") (name "V+") (class "Default")
      (node (ref "C15") (pin "+") (pinfunction "+_+") (pintype "passive"))
      (node (ref "C17") (pin "1") (pinfunction "1_1") (pintype "passive"))
      (node (ref "CR7") (pin "ANODE") (pinfunction "ANODE_ANODE") (pintype "passive"))
      (node (ref "D11") (pin "C") (pinfunction "C_C") (pintype "passive"))
      (node (ref "Q23") (pin "2") (pinfunction "D_2") (pintype "passive"))
      (node (ref "Q25") (pin "C") (pinfunction "C_C") (pintype "passive"))
      (node (ref "RLED+") (pin "1") (pinfunction "1_1") (pintype "passive"))
      (node (ref "V+") (pin "MP") (pinfunction "MP_MP") (pintype "passive"))
    )
    (net (code "65") (name "V-") (class "Default")
      (node (ref "C16") (pin "-") (pinfunction "-_-") (pintype "passive"))
      (node (ref "C18") (pin "2") (pinfunction "2_2") (pintype "passive"))
      (node (ref "CR8") (pin "1") (pinfunction "CATHODE_1") (pintype "passive"))
      (node (ref "CR8") (pin "2") (pinfunction "CATHODE_2") (pintype "passive"))
      (node (ref "CR8") (pin "CATHODE") (pinfunction "CATHODE_CATHODE") (pintype "passive"))
      (node (ref "D12") (pin "A") (pinfunction "A_A") (pintype "passive"))
      (node (ref "Q24") (pin "2") (pinfunction "D_2") (pintype "passive"))
      (node (ref "Q26") (pin "1") (pinfunction "C_1") (pintype "passive"))
      (node (ref "RLED-") (pin "2") (pinfunction "2_2") (pintype "passive"))
      (node (ref "V-") (pin "MP") (pinfunction "MP_MP") (pintype "passive"))
    )
    (net (code "66") (name "unconnected-(KK1-K-PadA2,5)") (class "Default")
      (node (ref "KK1") (pin "A2,5") (pinfunction "K_A2,5") (pintype "passive"))
    )
    (net (code "67") (name "unconnected-(KK1-K-PadB2,5)") (class "Default")
      (node (ref "KK1") (pin "B2,5") (pinfunction "K_B2,5") (pintype "passive"))
    )
    (net (code "68") (name "unconnected-(KK2-K-PadA2,5)") (class "Default")
      (node (ref "KK2") (pin "A2,5") (pinfunction "K_A2,5") (pintype "passive"))
    )
    (net (code "69") (name "unconnected-(KK2-K-PadB2,5)") (class "Default")
      (node (ref "KK2") (pin "B2,5") (pinfunction "K_B2,5") (pintype "passive"))
    )
    (net (code "70") (name "unconnected-(KK3-K-PadA2,5)") (class "Default")
      (node (ref "KK3") (pin "A2,5") (pinfunction "K_A2,5") (pintype "passive"))
    )
    (net (code "71") (name "unconnected-(KK3-K-PadB2,5)") (class "Default")
      (node (ref "KK3") (pin "B2,5") (pinfunction "K_B2,5") (pintype "passive"))
    )
    (net (code "72") (name "unconnected-(KK4-K-PadA2,5)") (class "Default")
      (node (ref "KK4") (pin "A2,5") (pinfunction "K_A2,5") (pintype "passive"))
    )
    (net (code "73") (name "unconnected-(KK4-K-PadB2,5)") (class "Default")
      (node (ref "KK4") (pin "B2,5") (pinfunction "K_B2,5") (pintype "passive"))
    )
  )
)
